# ZynqEMIO.net
KiCad netlist of a schematic drawn in Altium Designer
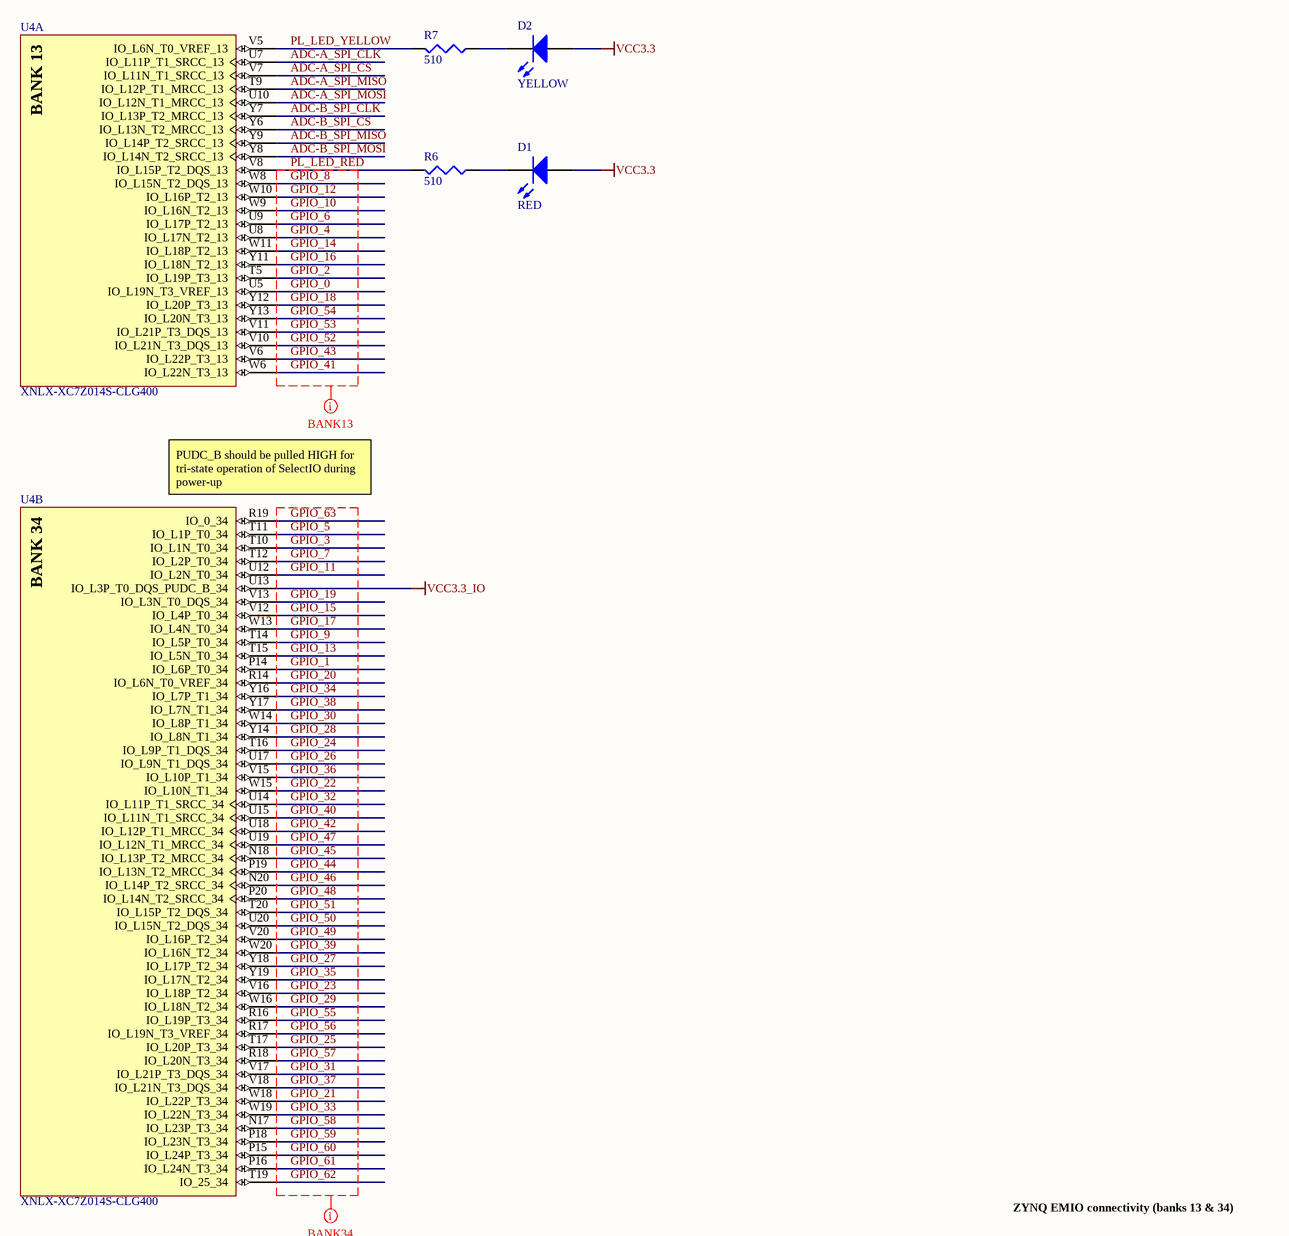
[diagram p0: ZynqEMIO.SchDoc]

(export (version "E")
  (design (tool "Eeschema 10.0.6"))
  (components
    (comp (ref "D1")
      (value "RED")
      (footprint "LED0603_M")
      (description "Light Emitting Diode")
      (fields (field (name "MANUFACTURER") "Lite-On") (field (name "PART") "LTST-C190KRKT"))
      (libsource (lib "CustomParts") (part "LED"))
    )
    (comp (ref "D2")
      (value "YELLOW")
      (footprint "LED0603_M")
      (description "Light Emitting Diode")
      (fields (field (name "MANUFACTURER") "Lite-On") (field (name "PART") "LTST-C190KSKT"))
      (libsource (lib "CustomParts") (part "LED"))
    )
    (comp (ref "R6")
      (value "510")
      (footprint "R0402_IPC_H")
      (description "Resistor")
      (fields (field (name "TOLERANCE") "1%") (field (name "MANUFACTURER") "Panasonic-ECG"))
      (libsource (lib "CustomParts") (part "Res"))
    )
    (comp (ref "R7")
      (value "510")
      (footprint "R0402_IPC_H")
      (description "Resistor")
      (fields (field (name "TOLERANCE") "1%") (field (name "MANUFACTURER") "Panasonic-ECG"))
      (libsource (lib "CustomParts") (part "Res"))
    )
    (comp (ref "U4")
      (value "XNLX-XC7Z014S-CLG400")
      (footprint "CLG400")
      (fields (field (name "MANUFACTURER") "Xilinx") (field (name "PART") "XC7Z014S-1CLG400C"))
      (libsource (lib "CustomParts") (part "XNLX-XC7Z020-CLG400"))
    )
  )
  (nets
    (net (code "1") (name "/ADC-A_SPI_CLK") (class "Default")
      (node (ref "U4") (pin "U7") (pinfunction "IO_L11P_T1_SRCC_13_U7") (pintype "bidirectional"))
    )
    (net (code "2") (name "/ADC-A_SPI_CS") (class "Default")
      (node (ref "U4") (pin "V7") (pinfunction "IO_L11N_T1_SRCC_13_V7") (pintype "bidirectional"))
    )
    (net (code "3") (name "/ADC-A_SPI_MISO") (class "Default")
      (node (ref "U4") (pin "T9") (pinfunction "IO_L12P_T1_MRCC_13_T9") (pintype "bidirectional"))
    )
    (net (code "4") (name "/ADC-A_SPI_MOSI") (class "Default")
      (node (ref "U4") (pin "U10") (pinfunction "IO_L12N_T1_MRCC_13_U10") (pintype "bidirectional"))
    )
    (net (code "5") (name "/ADC-B_SPI_CLK") (class "Default")
      (node (ref "U4") (pin "Y7") (pinfunction "IO_L13P_T2_MRCC_13_Y7") (pintype "bidirectional"))
    )
    (net (code "6") (name "/ADC-B_SPI_CS") (class "Default")
      (node (ref "U4") (pin "Y6") (pinfunction "IO_L13N_T2_MRCC_13_Y6") (pintype "bidirectional"))
    )
    (net (code "7") (name "/ADC-B_SPI_MISO") (class "Default")
      (node (ref "U4") (pin "Y9") (pinfunction "IO_L14P_T2_SRCC_13_Y9") (pintype "bidirectional"))
    )
    (net (code "8") (name "/ADC-B_SPI_MOSI") (class "Default")
      (node (ref "U4") (pin "Y8") (pinfunction "IO_L14N_T2_SRCC_13_Y8") (pintype "bidirectional"))
    )
    (net (code "9") (name "/GPIO_0") (class "Default")
      (node (ref "U4") (pin "U5") (pinfunction "IO_L19N_T3_VREF_13_U5") (pintype "bidirectional"))
    )
    (net (code "10") (name "/GPIO_1") (class "Default")
      (node (ref "U4") (pin "P14") (pinfunction "IO_L6P_T0_34_P14") (pintype "bidirectional"))
    )
    (net (code "11") (name "/GPIO_2") (class "Default")
      (node (ref "U4") (pin "T5") (pinfunction "IO_L19P_T3_13_T5") (pintype "bidirectional"))
    )
    (net (code "12") (name "/GPIO_3") (class "Default")
      (node (ref "U4") (pin "T10") (pinfunction "IO_L1N_T0_34_T10") (pintype "bidirectional"))
    )
    (net (code "13") (name "/GPIO_4") (class "Default")
      (node (ref "U4") (pin "U8") (pinfunction "IO_L17N_T2_13_U8") (pintype "bidirectional"))
    )
    (net (code "14") (name "/GPIO_5") (class "Default")
      (node (ref "U4") (pin "T11") (pinfunction "IO_L1P_T0_34_T11") (pintype "bidirectional"))
    )
    (net (code "15") (name "/GPIO_6") (class "Default")
      (node (ref "U4") (pin "U9") (pinfunction "IO_L17P_T2_13_U9") (pintype "bidirectional"))
    )
    (net (code "16") (name "/GPIO_7") (class "Default")
      (node (ref "U4") (pin "T12") (pinfunction "IO_L2P_T0_34_T12") (pintype "bidirectional"))
    )
    (net (code "17") (name "/GPIO_8") (class "Default")
      (node (ref "U4") (pin "W8") (pinfunction "IO_L15N_T2_DQS_13_W8") (pintype "bidirectional"))
    )
    (net (code "18") (name "/GPIO_9") (class "Default")
      (node (ref "U4") (pin "T14") (pinfunction "IO_L5P_T0_34_T14") (pintype "bidirectional"))
    )
    (net (code "19") (name "/GPIO_10") (class "Default")
      (node (ref "U4") (pin "W9") (pinfunction "IO_L16N_T2_13_W9") (pintype "bidirectional"))
    )
    (net (code "20") (name "/GPIO_11") (class "Default")
      (node (ref "U4") (pin "U12") (pinfunction "IO_L2N_T0_34_U12") (pintype "bidirectional"))
    )
    (net (code "21") (name "/GPIO_12") (class "Default")
      (node (ref "U4") (pin "W10") (pinfunction "IO_L16P_T2_13_W10") (pintype "bidirectional"))
    )
    (net (code "22") (name "/GPIO_13") (class "Default")
      (node (ref "U4") (pin "T15") (pinfunction "IO_L5N_T0_34_T15") (pintype "bidirectional"))
    )
    (net (code "23") (name "/GPIO_14") (class "Default")
      (node (ref "U4") (pin "W11") (pinfunction "IO_L18P_T2_13_W11") (pintype "bidirectional"))
    )
    (net (code "24") (name "/GPIO_15") (class "Default")
      (node (ref "U4") (pin "V12") (pinfunction "IO_L4P_T0_34_V12") (pintype "bidirectional"))
    )
    (net (code "25") (name "/GPIO_16") (class "Default")
      (node (ref "U4") (pin "Y11") (pinfunction "IO_L18N_T2_13_Y11") (pintype "bidirectional"))
    )
    (net (code "26") (name "/GPIO_17") (class "Default")
      (node (ref "U4") (pin "W13") (pinfunction "IO_L4N_T0_34_W13") (pintype "bidirectional"))
    )
    (net (code "27") (name "/GPIO_18") (class "Default")
      (node (ref "U4") (pin "Y12") (pinfunction "IO_L20P_T3_13_Y12") (pintype "bidirectional"))
    )
    (net (code "28") (name "/GPIO_19") (class "Default")
      (node (ref "U4") (pin "V13") (pinfunction "IO_L3N_T0_DQS_34_V13") (pintype "bidirectional"))
    )
    (net (code "29") (name "/GPIO_20") (class "Default")
      (node (ref "U4") (pin "R14") (pinfunction "IO_L6N_T0_VREF_34_R14") (pintype "bidirectional"))
    )
    (net (code "30") (name "/GPIO_21") (class "Default")
      (node (ref "U4") (pin "W18") (pinfunction "IO_L22P_T3_34_W18") (pintype "bidirectional"))
    )
    (net (code "31") (name "/GPIO_22") (class "Default")
      (node (ref "U4") (pin "W15") (pinfunction "IO_L10N_T1_34_W15") (pintype "bidirectional"))
    )
    (net (code "32") (name "/GPIO_23") (class "Default")
      (node (ref "U4") (pin "V16") (pinfunction "IO_L18P_T2_34_V16") (pintype "bidirectional"))
    )
    (net (code "33") (name "/GPIO_24") (class "Default")
      (node (ref "U4") (pin "T16") (pinfunction "IO_L9P_T1_DQS_34_T16") (pintype "bidirectional"))
    )
    (net (code "34") (name "/GPIO_25") (class "Default")
      (node (ref "U4") (pin "T17") (pinfunction "IO_L20P_T3_34_T17") (pintype "bidirectional"))
    )
    (net (code "35") (name "/GPIO_26") (class "Default")
      (node (ref "U4") (pin "U17") (pinfunction "IO_L9N_T1_DQS_34_U17") (pintype "bidirectional"))
    )
    (net (code "36") (name "/GPIO_27") (class "Default")
      (node (ref "U4") (pin "Y18") (pinfunction "IO_L17P_T2_34_Y18") (pintype "bidirectional"))
    )
    (net (code "37") (name "/GPIO_28") (class "Default")
      (node (ref "U4") (pin "Y14") (pinfunction "IO_L8N_T1_34_Y14") (pintype "bidirectional"))
    )
    (net (code "38") (name "/GPIO_29") (class "Default")
      (node (ref "U4") (pin "W16") (pinfunction "IO_L18N_T2_34_W16") (pintype "bidirectional"))
    )
    (net (code "39") (name "/GPIO_30") (class "Default")
      (node (ref "U4") (pin "W14") (pinfunction "IO_L8P_T1_34_W14") (pintype "bidirectional"))
    )
    (net (code "40") (name "/GPIO_31") (class "Default")
      (node (ref "U4") (pin "V17") (pinfunction "IO_L21P_T3_DQS_34_V17") (pintype "bidirectional"))
    )
    (net (code "41") (name "/GPIO_32") (class "Default")
      (node (ref "U4") (pin "U14") (pinfunction "IO_L11P_T1_SRCC_34_U14") (pintype "bidirectional"))
    )
    (net (code "42") (name "/GPIO_33") (class "Default")
      (node (ref "U4") (pin "W19") (pinfunction "IO_L22N_T3_34_W19") (pintype "bidirectional"))
    )
    (net (code "43") (name "/GPIO_34") (class "Default")
      (node (ref "U4") (pin "Y16") (pinfunction "IO_L7P_T1_34_Y16") (pintype "bidirectional"))
    )
    (net (code "44") (name "/GPIO_35") (class "Default")
      (node (ref "U4") (pin "Y19") (pinfunction "IO_L17N_T2_34_Y19") (pintype "bidirectional"))
    )
    (net (code "45") (name "/GPIO_36") (class "Default")
      (node (ref "U4") (pin "V15") (pinfunction "IO_L10P_T1_34_V15") (pintype "bidirectional"))
    )
    (net (code "46") (name "/GPIO_37") (class "Default")
      (node (ref "U4") (pin "V18") (pinfunction "IO_L21N_T3_DQS_34_V18") (pintype "bidirectional"))
    )
    (net (code "47") (name "/GPIO_38") (class "Default")
      (node (ref "U4") (pin "Y17") (pinfunction "IO_L7N_T1_34_Y17") (pintype "bidirectional"))
    )
    (net (code "48") (name "/GPIO_39") (class "Default")
      (node (ref "U4") (pin "W20") (pinfunction "IO_L16N_T2_34_W20") (pintype "bidirectional"))
    )
    (net (code "49") (name "/GPIO_40") (class "Default")
      (node (ref "U4") (pin "U15") (pinfunction "IO_L11N_T1_SRCC_34_U15") (pintype "bidirectional"))
    )
    (net (code "50") (name "/GPIO_41") (class "Default")
      (node (ref "U4") (pin "W6") (pinfunction "IO_L22N_T3_13_W6") (pintype "bidirectional"))
    )
    (net (code "51") (name "/GPIO_42") (class "Default")
      (node (ref "U4") (pin "U18") (pinfunction "IO_L12P_T1_MRCC_34_U18") (pintype "bidirectional"))
    )
    (net (code "52") (name "/GPIO_43") (class "Default")
      (node (ref "U4") (pin "V6") (pinfunction "IO_L22P_T3_13_V6") (pintype "bidirectional"))
    )
    (net (code "53") (name "/GPIO_44") (class "Default")
      (node (ref "U4") (pin "P19") (pinfunction "IO_L13N_T2_MRCC_34_P19") (pintype "bidirectional"))
    )
    (net (code "54") (name "/GPIO_45") (class "Default")
      (node (ref "U4") (pin "N18") (pinfunction "IO_L13P_T2_MRCC_34_N18") (pintype "bidirectional"))
    )
    (net (code "55") (name "/GPIO_46") (class "Default")
      (node (ref "U4") (pin "N20") (pinfunction "IO_L14P_T2_SRCC_34_N20") (pintype "bidirectional"))
    )
    (net (code "56") (name "/GPIO_47") (class "Default")
      (node (ref "U4") (pin "U19") (pinfunction "IO_L12N_T1_MRCC_34_U19") (pintype "bidirectional"))
    )
    (net (code "57") (name "/GPIO_48") (class "Default")
      (node (ref "U4") (pin "P20") (pinfunction "IO_L14N_T2_SRCC_34_P20") (pintype "bidirectional"))
    )
    (net (code "58") (name "/GPIO_49") (class "Default")
      (node (ref "U4") (pin "V20") (pinfunction "IO_L16P_T2_34_V20") (pintype "bidirectional"))
    )
    (net (code "59") (name "/GPIO_50") (class "Default")
      (node (ref "U4") (pin "U20") (pinfunction "IO_L15N_T2_DQS_34_U20") (pintype "bidirectional"))
    )
    (net (code "60") (name "/GPIO_51") (class "Default")
      (node (ref "U4") (pin "T20") (pinfunction "IO_L15P_T2_DQS_34_T20") (pintype "bidirectional"))
    )
    (net (code "61") (name "/GPIO_52") (class "Default")
      (node (ref "U4") (pin "V10") (pinfunction "IO_L21N_T3_DQS_13_V10") (pintype "bidirectional"))
    )
    (net (code "62") (name "/GPIO_53") (class "Default")
      (node (ref "U4") (pin "V11") (pinfunction "IO_L21P_T3_DQS_13_V11") (pintype "bidirectional"))
    )
    (net (code "63") (name "/GPIO_54") (class "Default")
      (node (ref "U4") (pin "Y13") (pinfunction "IO_L20N_T3_13_Y13") (pintype "bidirectional"))
    )
    (net (code "64") (name "/GPIO_55") (class "Default")
      (node (ref "U4") (pin "R16") (pinfunction "IO_L19P_T3_34_R16") (pintype "bidirectional"))
    )
    (net (code "65") (name "/GPIO_56") (class "Default")
      (node (ref "U4") (pin "R17") (pinfunction "IO_L19N_T3_VREF_34_R17") (pintype "bidirectional"))
    )
    (net (code "66") (name "/GPIO_57") (class "Default")
      (node (ref "U4") (pin "R18") (pinfunction "IO_L20N_T3_34_R18") (pintype "bidirectional"))
    )
    (net (code "67") (name "/GPIO_58") (class "Default")
      (node (ref "U4") (pin "N17") (pinfunction "IO_L23P_T3_34_N17") (pintype "bidirectional"))
    )
    (net (code "68") (name "/GPIO_59") (class "Default")
      (node (ref "U4") (pin "P18") (pinfunction "IO_L23N_T3_34_P18") (pintype "bidirectional"))
    )
    (net (code "69") (name "/GPIO_60") (class "Default")
      (node (ref "U4") (pin "P15") (pinfunction "IO_L24P_T3_34_P15") (pintype "bidirectional"))
    )
    (net (code "70") (name "/GPIO_61") (class "Default")
      (node (ref "U4") (pin "P16") (pinfunction "IO_L24N_T3_34_P16") (pintype "bidirectional"))
    )
    (net (code "71") (name "/GPIO_62") (class "Default")
      (node (ref "U4") (pin "T19") (pinfunction "IO_25_34_T19") (pintype "bidirectional"))
    )
    (net (code "72") (name "/GPIO_63") (class "Default")
      (node (ref "U4") (pin "R19") (pinfunction "IO_0_34_R19") (pintype "bidirectional"))
    )
    (net (code "73") (name "/PL_LED_RED") (class "Default")
      (node (ref "R6") (pin "2") (pinfunction "2_2") (pintype "passive"))
      (node (ref "U4") (pin "V8") (pinfunction "IO_L15P_T2_DQS_13_V8") (pintype "bidirectional"))
    )
    (net (code "74") (name "/PL_LED_YELLOW") (class "Default")
      (node (ref "R7") (pin "2") (pinfunction "2_2") (pintype "passive"))
      (node (ref "U4") (pin "V5") (pinfunction "IO_L6N_T0_VREF_13_V5") (pintype "bidirectional"))
    )
    (net (code "75") (name "Net-(D1-K)") (class "Default")
      (node (ref "D1") (pin "2") (pinfunction "K_2") (pintype "passive"))
      (node (ref "R6") (pin "1") (pinfunction "1_1") (pintype "passive"))
    )
    (net (code "76") (name "Net-(D2-K)") (class "Default")
      (node (ref "D2") (pin "2") (pinfunction "K_2") (pintype "passive"))
      (node (ref "R7") (pin "1") (pinfunction "1_1") (pintype "passive"))
    )
    (net (code "77") (name "VCC3.3") (class "Default")
      (node (ref "D1") (pin "1") (pinfunction "A_1") (pintype "passive"))
      (node (ref "D2") (pin "1") (pinfunction "A_1") (pintype "passive"))
    )
    (net (code "78") (name "VCC3.3_IO") (class "Default")
      (node (ref "U4") (pin "U13") (pinfunction "IO_L3P_T0_DQS_PUDC_B_34_U13") (pintype "bidirectional"))
    )
  )
)
